# Feedback.net
KiCad netlist of a schematic drawn in Altium Designer
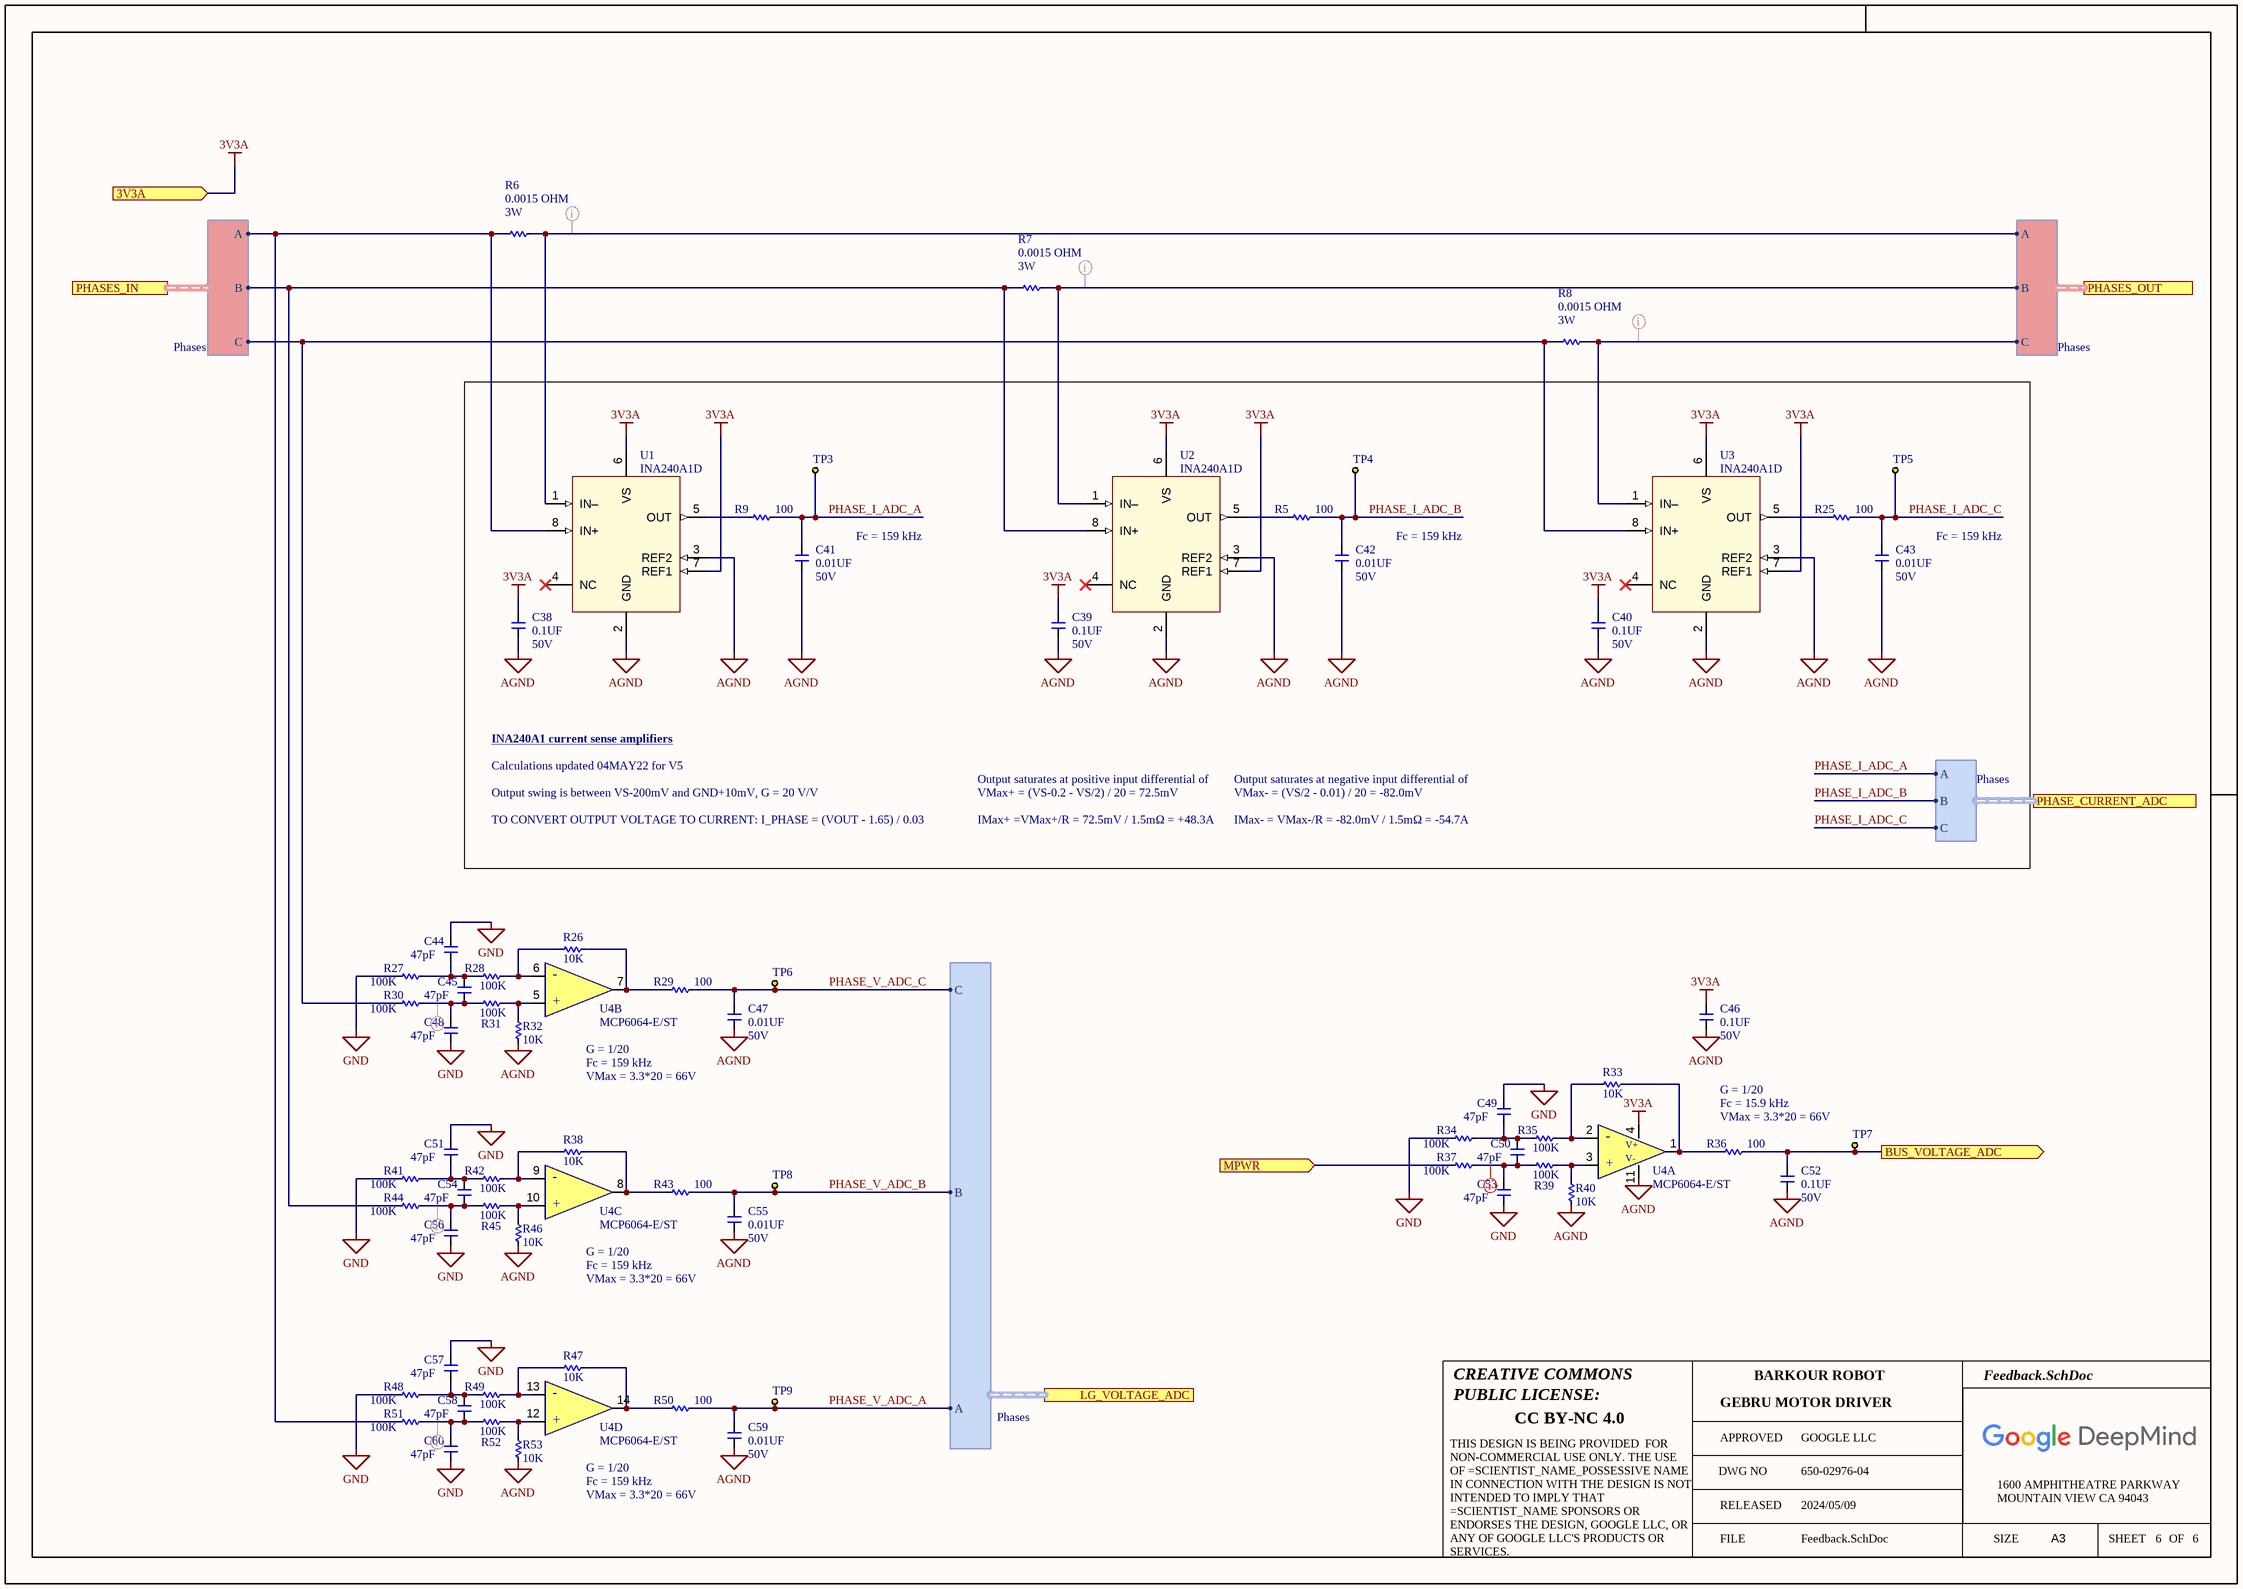
[diagram p0: Feedback.SchDoc]

(export (version "E")
  (design (tool "Eeschema 10.0.6"))
  (components
    (comp (ref "C38")
      (value "0.1UF")
      (footprint "C0402")
      (description "CAP, CER, X5R, 0.1uF, 10%, 50V, 0402, 0.55mm")
      (fields (field (name "MFG") "YAGEO") (field (name "VOLTAGE") "50V") (field (name "TOLERANCE") "10%"))
      (libsource (lib "AltiumReleaseLibDB") (part "__Template_Cap"))
    )
    (comp (ref "C39")
      (value "0.1UF")
      (footprint "C0402")
      (description "CAP, CER, X5R, 0.1uF, 10%, 50V, 0402, 0.55mm")
      (fields (field (name "MFG") "YAGEO") (field (name "VOLTAGE") "50V") (field (name "TOLERANCE") "10%"))
      (libsource (lib "AltiumReleaseLibDB") (part "__Template_Cap"))
    )
    (comp (ref "C40")
      (value "0.1UF")
      (footprint "C0402")
      (description "CAP, CER, X5R, 0.1uF, 10%, 50V, 0402, 0.55mm")
      (fields (field (name "MFG") "YAGEO") (field (name "VOLTAGE") "50V") (field (name "TOLERANCE") "10%"))
      (libsource (lib "AltiumReleaseLibDB") (part "__Template_Cap"))
    )
    (comp (ref "C41")
      (value "0.01UF")
      (footprint "C0402")
      (description "CAP, CER, X7R, 0.01uF, 50V, 20%, 0402, 0.56mm T")
      (fields (field (name "MFG") "KEMET") (field (name "VOLTAGE") "50V") (field (name "TOLERANCE") "20%"))
      (libsource (lib "AltiumReleaseLibDB") (part "__Template_Cap"))
    )
    (comp (ref "C42")
      (value "0.01UF")
      (footprint "C0402")
      (description "CAP, CER, X7R, 0.01uF, 50V, 20%, 0402, 0.56mm T")
      (fields (field (name "MFG") "KEMET") (field (name "VOLTAGE") "50V") (field (name "TOLERANCE") "20%"))
      (libsource (lib "AltiumReleaseLibDB") (part "__Template_Cap"))
    )
    (comp (ref "C43")
      (value "0.01UF")
      (footprint "C0402")
      (description "CAP, CER, X7R, 0.01uF, 50V, 20%, 0402, 0.56mm T")
      (fields (field (name "MFG") "KEMET") (field (name "VOLTAGE") "50V") (field (name "TOLERANCE") "20%"))
      (libsource (lib "AltiumReleaseLibDB") (part "__Template_Cap"))
    )
    (comp (ref "C44")
      (value "47pF")
      (footprint "C0402")
      (description "CAP, CER, C0G, 47PF, 5%, 50V, 0402")
      (fields (field (name "MFG") "TDK") (field (name "VOLTAGE") "50V"))
      (libsource (lib "AltiumReleaseLibDB") (part "__Template_Cap"))
    )
    (comp (ref "C45")
      (value "47pF")
      (footprint "C0402")
      (description "CAP, CER, C0G, 47PF, 5%, 50V, 0402")
      (fields (field (name "MFG") "TDK") (field (name "VOLTAGE") "50V"))
      (libsource (lib "AltiumReleaseLibDB") (part "__Template_Cap"))
    )
    (comp (ref "C46")
      (value "0.1UF")
      (footprint "C0402")
      (description "CAP, CER, X5R, 0.1uF, 10%, 50V, 0402, 0.55mm")
      (fields (field (name "MFG") "YAGEO") (field (name "VOLTAGE") "50V") (field (name "TOLERANCE") "10%"))
      (libsource (lib "AltiumReleaseLibDB") (part "__Template_Cap"))
    )
    (comp (ref "C47")
      (value "0.01UF")
      (footprint "C0402")
      (description "CAP, CER, X7R, 0.01uF, 50V, 20%, 0402, 0.56mm T")
      (fields (field (name "MFG") "KEMET") (field (name "VOLTAGE") "50V") (field (name "TOLERANCE") "20%"))
      (libsource (lib "AltiumReleaseLibDB") (part "__Template_Cap"))
    )
    (comp (ref "C48")
      (value "47pF")
      (footprint "C0402")
      (description "CAP, CER, C0G, 47PF, 5%, 50V, 0402")
      (fields (field (name "MFG") "TDK") (field (name "VOLTAGE") "50V"))
      (libsource (lib "AltiumReleaseLibDB") (part "__Template_Cap"))
    )
    (comp (ref "C49")
      (value "47pF")
      (footprint "C0402")
      (description "CAP, CER, C0G, 47PF, 5%, 50V, 0402")
      (fields (field (name "MFG") "TDK") (field (name "VOLTAGE") "50V"))
      (libsource (lib "AltiumReleaseLibDB") (part "__Template_Cap"))
    )
    (comp (ref "C50")
      (value "47pF")
      (footprint "C0402")
      (description "CAP, CER, C0G, 47PF, 5%, 50V, 0402")
      (fields (field (name "MFG") "TDK") (field (name "VOLTAGE") "50V"))
      (libsource (lib "AltiumReleaseLibDB") (part "__Template_Cap"))
    )
    (comp (ref "C51")
      (value "47pF")
      (footprint "C0402")
      (description "CAP, CER, C0G, 47PF, 5%, 50V, 0402")
      (fields (field (name "MFG") "TDK") (field (name "VOLTAGE") "50V"))
      (libsource (lib "AltiumReleaseLibDB") (part "__Template_Cap"))
    )
    (comp (ref "C52")
      (value "0.1UF")
      (footprint "C0402")
      (description "CAP, CER, X5R, 0.1uF, 10%, 50V, 0402, 0.55mm")
      (fields (field (name "MFG") "YAGEO") (field (name "VOLTAGE") "50V") (field (name "TOLERANCE") "10%"))
      (libsource (lib "AltiumReleaseLibDB") (part "__Template_Cap"))
    )
    (comp (ref "C53")
      (value "47pF")
      (footprint "C0402")
      (description "CAP, CER, C0G, 47PF, 5%, 50V, 0402")
      (fields (field (name "MFG") "TDK") (field (name "VOLTAGE") "50V"))
      (libsource (lib "AltiumReleaseLibDB") (part "__Template_Cap"))
    )
    (comp (ref "C54")
      (value "47pF")
      (footprint "C0402")
      (description "CAP, CER, C0G, 47PF, 5%, 50V, 0402")
      (fields (field (name "MFG") "TDK") (field (name "VOLTAGE") "50V"))
      (libsource (lib "AltiumReleaseLibDB") (part "__Template_Cap"))
    )
    (comp (ref "C55")
      (value "0.01UF")
      (footprint "C0402")
      (description "CAP, CER, X7R, 0.01uF, 50V, 20%, 0402, 0.56mm T")
      (fields (field (name "MFG") "KEMET") (field (name "VOLTAGE") "50V") (field (name "TOLERANCE") "20%"))
      (libsource (lib "AltiumReleaseLibDB") (part "__Template_Cap"))
    )
    (comp (ref "C56")
      (value "47pF")
      (footprint "C0402")
      (description "CAP, CER, C0G, 47PF, 5%, 50V, 0402")
      (fields (field (name "MFG") "TDK") (field (name "VOLTAGE") "50V"))
      (libsource (lib "AltiumReleaseLibDB") (part "__Template_Cap"))
    )
    (comp (ref "C57")
      (value "47pF")
      (footprint "C0402")
      (description "CAP, CER, C0G, 47PF, 5%, 50V, 0402")
      (fields (field (name "MFG") "TDK") (field (name "VOLTAGE") "50V"))
      (libsource (lib "AltiumReleaseLibDB") (part "__Template_Cap"))
    )
    (comp (ref "C58")
      (value "47pF")
      (footprint "C0402")
      (description "CAP, CER, C0G, 47PF, 5%, 50V, 0402")
      (fields (field (name "MFG") "TDK") (field (name "VOLTAGE") "50V"))
      (libsource (lib "AltiumReleaseLibDB") (part "__Template_Cap"))
    )
    (comp (ref "C59")
      (value "0.01UF")
      (footprint "C0402")
      (description "CAP, CER, X7R, 0.01uF, 50V, 20%, 0402, 0.56mm T")
      (fields (field (name "MFG") "KEMET") (field (name "VOLTAGE") "50V") (field (name "TOLERANCE") "20%"))
      (libsource (lib "AltiumReleaseLibDB") (part "__Template_Cap"))
    )
    (comp (ref "C60")
      (value "47pF")
      (footprint "C0402")
      (description "CAP, CER, C0G, 47PF, 5%, 50V, 0402")
      (fields (field (name "MFG") "TDK") (field (name "VOLTAGE") "50V"))
      (libsource (lib "AltiumReleaseLibDB") (part "__Template_Cap"))
    )
    (comp (ref "R5")
      (value "100")
      (footprint "RES 0402_1005 RF")
      (description "RES, 100, 1%, 1/10W, 0402, AUTO GRADE")
      (fields (field (name "MFG") "PANASONIC") (field (name "POWER") "1/10W"))
      (libsource (lib "AltiumReleaseLibDB") (part "__Template_Resistor"))
    )
    (comp (ref "R6")
      (value "0.0015 OHM")
      (footprint "R2512_H0.8MM")
      (description "RES, 0.0015, 1%, 3W, 2512")
      (fields
        (field (name "MFG") "TE Connectivity Passive Product")
        (field (name "POWER") "3W")
        (field (name "TOLERANCE") "1%")
      )
      (libsource (lib "AltiumReleaseLibDB") (part "__Template_Resistor"))
    )
    (comp (ref "R7")
      (value "0.0015 OHM")
      (footprint "R2512_H0.8MM")
      (description "RES, 0.0015, 1%, 3W, 2512")
      (fields
        (field (name "MFG") "TE Connectivity Passive Product")
        (field (name "POWER") "3W")
        (field (name "TOLERANCE") "1%")
      )
      (libsource (lib "AltiumReleaseLibDB") (part "__Template_Resistor"))
    )
    (comp (ref "R8")
      (value "0.0015 OHM")
      (footprint "R2512_H0.8MM")
      (description "RES, 0.0015, 1%, 3W, 2512")
      (fields
        (field (name "MFG") "TE Connectivity Passive Product")
        (field (name "POWER") "3W")
        (field (name "TOLERANCE") "1%")
      )
      (libsource (lib "AltiumReleaseLibDB") (part "__Template_Resistor"))
    )
    (comp (ref "R9")
      (value "100")
      (footprint "R0402")
      (description "RES, 100, 1%, 1/10W, 0402, AUTO GRADE")
      (fields (field (name "MFG") "PANASONIC") (field (name "POWER") "1/10W"))
      (libsource (lib "AltiumReleaseLibDB") (part "__Template_Resistor"))
    )
    (comp (ref "R25")
      (value "100")
      (footprint "R0402")
      (description "RES, 100, 1%, 1/10W, 0402, AUTO GRADE")
      (fields (field (name "MFG") "PANASONIC") (field (name "POWER") "1/10W"))
      (libsource (lib "AltiumReleaseLibDB") (part "__Template_Resistor"))
    )
    (comp (ref "R26")
      (value "10K")
      (footprint "R0402")
      (description "RES, 10K, 1%, 1/10W, 0402, AUTOGRADE")
      (fields (field (name "MFG") "PANASONIC") (field (name "POWER") "1/10W"))
      (libsource (lib "AltiumReleaseLibDB") (part "__Template_Resistor"))
    )
    (comp (ref "R27")
      (value "100K")
      (footprint "R0603")
      (description "RES, 100K, 1%, 1/10W, 0603, AUTO GRADE")
      (fields (field (name "MFG") "PANASONIC") (field (name "POWER") "1/10W"))
      (libsource (lib "AltiumReleaseLibDB") (part "__Template_Resistor"))
    )
    (comp (ref "R28")
      (value "100K")
      (footprint "R0603")
      (description "RES, 100K, 1%, 1/10W, 0603, AUTO GRADE")
      (fields (field (name "MFG") "PANASONIC") (field (name "POWER") "1/10W"))
      (libsource (lib "AltiumReleaseLibDB") (part "__Template_Resistor"))
    )
    (comp (ref "R29")
      (value "100")
      (footprint "R0402")
      (description "RES, 100, 1%, 1/10W, 0402, AUTO GRADE")
      (fields (field (name "MFG") "PANASONIC") (field (name "POWER") "1/10W"))
      (libsource (lib "AltiumReleaseLibDB") (part "__Template_Resistor"))
    )
    (comp (ref "R30")
      (value "100K")
      (footprint "R0603")
      (description "RES, 100K, 1%, 1/10W, 0603, AUTO GRADE")
      (fields (field (name "MFG") "PANASONIC") (field (name "POWER") "1/10W"))
      (libsource (lib "AltiumReleaseLibDB") (part "__Template_Resistor"))
    )
    (comp (ref "R31")
      (value "100K")
      (footprint "R0603")
      (description "RES, 100K, 1%, 1/10W, 0603, AUTO GRADE")
      (fields (field (name "MFG") "PANASONIC") (field (name "POWER") "1/10W"))
      (libsource (lib "AltiumReleaseLibDB") (part "__Template_Resistor"))
    )
    (comp (ref "R32")
      (value "10K")
      (footprint "R0402")
      (description "RES, 10K, 1%, 1/10W, 0402, AUTOGRADE")
      (fields (field (name "MFG") "PANASONIC") (field (name "POWER") "1/10W"))
      (libsource (lib "AltiumReleaseLibDB") (part "__Template_Resistor"))
    )
    (comp (ref "R33")
      (value "10K")
      (footprint "R0402")
      (description "RES, 10K, 1%, 1/10W, 0402, AUTOGRADE")
      (fields (field (name "MFG") "PANASONIC") (field (name "POWER") "1/10W"))
      (libsource (lib "AltiumReleaseLibDB") (part "__Template_Resistor"))
    )
    (comp (ref "R34")
      (value "100K")
      (footprint "R0603")
      (description "RES, 100K, 1%, 1/10W, 0603, AUTO GRADE")
      (fields (field (name "MFG") "PANASONIC") (field (name "POWER") "1/10W"))
      (libsource (lib "AltiumReleaseLibDB") (part "__Template_Resistor"))
    )
    (comp (ref "R35")
      (value "100K")
      (footprint "R0603")
      (description "RES, 100K, 1%, 1/10W, 0603, AUTO GRADE")
      (fields (field (name "MFG") "PANASONIC") (field (name "POWER") "1/10W"))
      (libsource (lib "AltiumReleaseLibDB") (part "__Template_Resistor"))
    )
    (comp (ref "R36")
      (value "100")
      (footprint "R0402")
      (description "RES, 100, 1%, 1/10W, 0402, AUTO GRADE")
      (fields (field (name "MFG") "PANASONIC") (field (name "POWER") "1/10W"))
      (libsource (lib "AltiumReleaseLibDB") (part "__Template_Resistor"))
    )
    (comp (ref "R37")
      (value "100K")
      (footprint "R0603")
      (description "RES, 100K, 1%, 1/10W, 0603, AUTO GRADE")
      (fields (field (name "MFG") "PANASONIC") (field (name "POWER") "1/10W"))
      (libsource (lib "AltiumReleaseLibDB") (part "__Template_Resistor"))
    )
    (comp (ref "R38")
      (value "10K")
      (footprint "R0402")
      (description "RES, 10K, 1%, 1/10W, 0402, AUTOGRADE")
      (fields (field (name "MFG") "PANASONIC") (field (name "POWER") "1/10W"))
      (libsource (lib "AltiumReleaseLibDB") (part "__Template_Resistor"))
    )
    (comp (ref "R39")
      (value "100K")
      (footprint "R0603")
      (description "RES, 100K, 1%, 1/10W, 0603, AUTO GRADE")
      (fields (field (name "MFG") "PANASONIC") (field (name "POWER") "1/10W"))
      (libsource (lib "AltiumReleaseLibDB") (part "__Template_Resistor"))
    )
    (comp (ref "R40")
      (value "10K")
      (footprint "R0402")
      (description "RES, 10K, 1%, 1/10W, 0402, AUTOGRADE")
      (fields (field (name "MFG") "PANASONIC") (field (name "POWER") "1/10W"))
      (libsource (lib "AltiumReleaseLibDB") (part "__Template_Resistor"))
    )
    (comp (ref "R41")
      (value "100K")
      (footprint "R0603")
      (description "RES, 100K, 1%, 1/10W, 0603, AUTO GRADE")
      (fields (field (name "MFG") "PANASONIC") (field (name "POWER") "1/10W"))
      (libsource (lib "AltiumReleaseLibDB") (part "__Template_Resistor"))
    )
    (comp (ref "R42")
      (value "100K")
      (footprint "R0603")
      (description "RES, 100K, 1%, 1/10W, 0603, AUTO GRADE")
      (fields (field (name "MFG") "PANASONIC") (field (name "POWER") "1/10W"))
      (libsource (lib "AltiumReleaseLibDB") (part "__Template_Resistor"))
    )
    (comp (ref "R43")
      (value "100")
      (footprint "R0402")
      (description "RES, 100, 1%, 1/10W, 0402, AUTO GRADE")
      (fields (field (name "MFG") "PANASONIC") (field (name "POWER") "1/10W"))
      (libsource (lib "AltiumReleaseLibDB") (part "__Template_Resistor"))
    )
    (comp (ref "R44")
      (value "100K")
      (footprint "R0603")
      (description "RES, 100K, 1%, 1/10W, 0603, AUTO GRADE")
      (fields (field (name "MFG") "PANASONIC") (field (name "POWER") "1/10W"))
      (libsource (lib "AltiumReleaseLibDB") (part "__Template_Resistor"))
    )
    (comp (ref "R45")
      (value "100K")
      (footprint "R0603")
      (description "RES, 100K, 1%, 1/10W, 0603, AUTO GRADE")
      (fields (field (name "MFG") "PANASONIC") (field (name "POWER") "1/10W"))
      (libsource (lib "AltiumReleaseLibDB") (part "__Template_Resistor"))
    )
    (comp (ref "R46")
      (value "10K")
      (footprint "R0402")
      (description "RES, 10K, 1%, 1/10W, 0402, AUTOGRADE")
      (fields (field (name "MFG") "PANASONIC") (field (name "POWER") "1/10W"))
      (libsource (lib "AltiumReleaseLibDB") (part "__Template_Resistor"))
    )
    (comp (ref "R47")
      (value "10K")
      (footprint "R0402")
      (description "RES, 10K, 1%, 1/10W, 0402, AUTOGRADE")
      (fields (field (name "MFG") "PANASONIC") (field (name "POWER") "1/10W"))
      (libsource (lib "AltiumReleaseLibDB") (part "__Template_Resistor"))
    )
    (comp (ref "R48")
      (value "100K")
      (footprint "R0603")
      (description "RES, 100K, 1%, 1/10W, 0603, AUTO GRADE")
      (fields (field (name "MFG") "PANASONIC") (field (name "POWER") "1/10W"))
      (libsource (lib "AltiumReleaseLibDB") (part "__Template_Resistor"))
    )
    (comp (ref "R49")
      (value "100K")
      (footprint "R0603")
      (description "RES, 100K, 1%, 1/10W, 0603, AUTO GRADE")
      (fields (field (name "MFG") "PANASONIC") (field (name "POWER") "1/10W"))
      (libsource (lib "AltiumReleaseLibDB") (part "__Template_Resistor"))
    )
    (comp (ref "R50")
      (value "100")
      (footprint "R0402")
      (description "RES, 100, 1%, 1/10W, 0402, AUTO GRADE")
      (fields (field (name "MFG") "PANASONIC") (field (name "POWER") "1/10W"))
      (libsource (lib "AltiumReleaseLibDB") (part "__Template_Resistor"))
    )
    (comp (ref "R51")
      (value "100K")
      (footprint "R0603")
      (description "RES, 100K, 1%, 1/10W, 0603, AUTO GRADE")
      (fields (field (name "MFG") "PANASONIC") (field (name "POWER") "1/10W"))
      (libsource (lib "AltiumReleaseLibDB") (part "__Template_Resistor"))
    )
    (comp (ref "R52")
      (value "100K")
      (footprint "R0603")
      (description "RES, 100K, 1%, 1/10W, 0603, AUTO GRADE")
      (fields (field (name "MFG") "PANASONIC") (field (name "POWER") "1/10W"))
      (libsource (lib "AltiumReleaseLibDB") (part "__Template_Resistor"))
    )
    (comp (ref "R53")
      (value "10K")
      (footprint "R0402")
      (description "RES, 10K, 1%, 1/10W, 0402, AUTOGRADE")
      (fields (field (name "MFG") "PANASONIC") (field (name "POWER") "1/10W"))
      (libsource (lib "AltiumReleaseLibDB") (part "__Template_Resistor"))
    )
    (comp (ref "TP3")
      (value "TEST_KEYSTONE5015")
      (footprint "TP_KEYSTONE_5015")
      (description "PC TEST POINT MINIATURE SMT")
      (fields
        (field (name "MANUFACTURER") "Keystone Electronics")
        (field (name "MANUFACTURER PART NUMBER") "5015")
      )
      (libsource (lib "miscellaneous") (part "TEST_KEYSTONE5015"))
    )
    (comp (ref "TP4")
      (value "TEST_KEYSTONE5015")
      (footprint "TP_KEYSTONE_5015")
      (description "PC TEST POINT MINIATURE SMT")
      (fields
        (field (name "MANUFACTURER") "Keystone Electronics")
        (field (name "MANUFACTURER PART NUMBER") "5015")
      )
      (libsource (lib "miscellaneous") (part "TEST_KEYSTONE5015"))
    )
    (comp (ref "TP5")
      (value "TEST_KEYSTONE5015")
      (footprint "TP_KEYSTONE_5015")
      (description "PC TEST POINT MINIATURE SMT")
      (fields
        (field (name "MANUFACTURER") "Keystone Electronics")
        (field (name "MANUFACTURER PART NUMBER") "5015")
      )
      (libsource (lib "miscellaneous") (part "TEST_KEYSTONE5015"))
    )
    (comp (ref "TP6")
      (value "TEST_KEYSTONE5015")
      (footprint "TP_KEYSTONE_5015")
      (description "PC TEST POINT MINIATURE SMT")
      (fields
        (field (name "MANUFACTURER") "Keystone Electronics")
        (field (name "MANUFACTURER PART NUMBER") "5015")
      )
      (libsource (lib "miscellaneous") (part "TEST_KEYSTONE5015"))
    )
    (comp (ref "TP7")
      (value "TEST_KEYSTONE5015")
      (footprint "TP_KEYSTONE_5015")
      (description "PC TEST POINT MINIATURE SMT")
      (fields
        (field (name "MANUFACTURER") "Keystone Electronics")
        (field (name "MANUFACTURER PART NUMBER") "5015")
      )
      (libsource (lib "miscellaneous") (part "TEST_KEYSTONE5015"))
    )
    (comp (ref "TP8")
      (value "TEST_KEYSTONE5015")
      (footprint "TP_KEYSTONE_5015")
      (description "PC TEST POINT MINIATURE SMT")
      (fields
        (field (name "MANUFACTURER") "Keystone Electronics")
        (field (name "MANUFACTURER PART NUMBER") "5015")
      )
      (libsource (lib "miscellaneous") (part "TEST_KEYSTONE5015"))
    )
    (comp (ref "TP9")
      (value "TEST_KEYSTONE5015")
      (footprint "TP_KEYSTONE_5015")
      (description "PC TEST POINT MINIATURE SMT")
      (fields
        (field (name "MANUFACTURER") "Keystone Electronics")
        (field (name "MANUFACTURER PART NUMBER") "5015")
      )
      (libsource (lib "miscellaneous") (part "TEST_KEYSTONE5015"))
    )
    (comp (ref "U1")
      (value "INA240A1D")
      (footprint "TI SOIC-8 D0008A")
      (fields (field (name "MANUFACTURER") "Texas Instruments"))
      (libsource (lib "MiscSch1") (part "INA240A1"))
    )
    (comp (ref "U2")
      (value "INA240A1D")
      (footprint "TI SOIC-8 D0008A")
      (fields (field (name "MANUFACTURER") "Texas Instruments"))
      (libsource (lib "MiscSch1") (part "INA240A1"))
    )
    (comp (ref "U3")
      (value "INA240A1D")
      (footprint "TI SOIC-8 D0008A")
      (fields (field (name "MANUFACTURER") "Texas Instruments"))
      (libsource (lib "MiscSch1") (part "INA240A1"))
    )
    (comp (ref "U4")
      (value "MCP6064")
      (footprint "14TSSOP65")
      (description "Microchip MCP6064-E/ST; Quad Op Amp; 0.73MHz CMOS; Rail to Rail; 3V; 5V; 14-Pin TSSOP")
      (fields
        (field (name "MANUFACTURER") "Microchip")
        (field (name "MANUFACTURER PART NUMBER") "MCP6064-E/ST")
      )
      (libsource (lib "MiscSch1") (part "MICROCHIP_MCP6064"))
    )
  )
  (nets
    (net (code "2") (name "/BUS_VOLTAGE_ADC") (class "Default")
      (node (ref "C52") (pin "1") (pintype "passive"))
      (node (ref "R36") (pin "2") (pintype "passive"))
      (node (ref "TP7") (pin "1") (pintype "passive"))
    )
    (net (code "3") (name "/MPWR") (class "Default") (node (ref "R37") (pin "1") (pintype "passive")))
    (net (code "4") (name "/PHASE_I_ADC_A") (class "Default")
      (node (ref "C41") (pin "1") (pintype "passive"))
      (node (ref "R9") (pin "2") (pintype "passive"))
      (node (ref "TP3") (pin "1") (pintype "passive"))
    )
    (net (code "5") (name "/PHASE_I_ADC_B") (class "Default")
      (node (ref "C42") (pin "1") (pintype "passive"))
      (node (ref "R5") (pin "2") (pintype "passive"))
      (node (ref "TP4") (pin "1") (pintype "passive"))
    )
    (net (code "6") (name "/PHASE_I_ADC_C") (class "Default")
      (node (ref "C43") (pin "1") (pintype "passive"))
      (node (ref "R25") (pin "2") (pintype "passive"))
      (node (ref "TP5") (pin "1") (pintype "passive"))
    )
    (net (code "7") (name "/PHASE_V_ADC_A") (class "Default")
      (node (ref "C59") (pin "1") (pintype "passive"))
      (node (ref "R50") (pin "2") (pintype "passive"))
      (node (ref "TP9") (pin "1") (pintype "passive"))
    )
    (net (code "8") (name "/PHASE_V_ADC_B") (class "Default")
      (node (ref "C55") (pin "1") (pintype "passive"))
      (node (ref "R43") (pin "2") (pintype "passive"))
      (node (ref "TP8") (pin "1") (pintype "passive"))
    )
    (net (code "9") (name "/PHASE_V_ADC_C") (class "Default")
      (node (ref "C47") (pin "1") (pintype "passive"))
      (node (ref "R29") (pin "2") (pintype "passive"))
      (node (ref "TP6") (pin "1") (pintype "passive"))
    )
    (net (code "11") (name "3V3A") (class "Default")
      (node (ref "C38") (pin "1") (pintype "passive"))
      (node (ref "C39") (pin "1") (pintype "passive"))
      (node (ref "C40") (pin "1") (pintype "passive"))
      (node (ref "C46") (pin "1") (pintype "passive"))
      (node (ref "U1") (pin "6") (pinfunction "VS_6") (pintype "power_in"))
      (node (ref "U1") (pin "7") (pinfunction "REF1_7") (pintype "input"))
      (node (ref "U2") (pin "6") (pinfunction "VS_6") (pintype "power_in"))
      (node (ref "U2") (pin "7") (pinfunction "REF1_7") (pintype "input"))
      (node (ref "U3") (pin "6") (pinfunction "VS_6") (pintype "power_in"))
      (node (ref "U3") (pin "7") (pinfunction "REF1_7") (pintype "input"))
      (node (ref "U4") (pin "4") (pinfunction "4_4") (pintype "passive"))
    )
    (net (code "12") (name "AGND") (class "Default")
      (node (ref "C38") (pin "2") (pintype "passive"))
      (node (ref "C39") (pin "2") (pintype "passive"))
      (node (ref "C40") (pin "2") (pintype "passive"))
      (node (ref "C41") (pin "2") (pintype "passive"))
      (node (ref "C42") (pin "2") (pintype "passive"))
      (node (ref "C43") (pin "2") (pintype "passive"))
      (node (ref "C46") (pin "2") (pintype "passive"))
      (node (ref "C47") (pin "2") (pintype "passive"))
      (node (ref "C52") (pin "2") (pintype "passive"))
      (node (ref "C55") (pin "2") (pintype "passive"))
      (node (ref "C59") (pin "2") (pintype "passive"))
      (node (ref "R32") (pin "1") (pintype "passive"))
      (node (ref "R40") (pin "1") (pintype "passive"))
      (node (ref "R46") (pin "1") (pintype "passive"))
      (node (ref "R53") (pin "1") (pintype "passive"))
      (node (ref "U1") (pin "2") (pinfunction "GND_2") (pintype "power_in"))
      (node (ref "U1") (pin "3") (pinfunction "REF2_3") (pintype "input"))
      (node (ref "U2") (pin "2") (pinfunction "GND_2") (pintype "power_in"))
      (node (ref "U2") (pin "3") (pinfunction "REF2_3") (pintype "input"))
      (node (ref "U3") (pin "2") (pinfunction "GND_2") (pintype "power_in"))
      (node (ref "U3") (pin "3") (pinfunction "REF2_3") (pintype "input"))
      (node (ref "U4") (pin "11") (pinfunction "11_11") (pintype "passive"))
    )
    (net (code "13") (name "GND") (class "Default")
      (node (ref "C44") (pin "2") (pintype "passive"))
      (node (ref "C48") (pin "1") (pintype "passive"))
      (node (ref "C49") (pin "2") (pintype "passive"))
      (node (ref "C51") (pin "2") (pintype "passive"))
      (node (ref "C53") (pin "1") (pintype "passive"))
      (node (ref "C56") (pin "1") (pintype "passive"))
      (node (ref "C57") (pin "2") (pintype "passive"))
      (node (ref "C60") (pin "1") (pintype "passive"))
      (node (ref "R27") (pin "1") (pintype "passive"))
      (node (ref "R34") (pin "1") (pintype "passive"))
      (node (ref "R41") (pin "1") (pintype "passive"))
      (node (ref "R48") (pin "1") (pintype "passive"))
    )
    (net (code "14") (name "Net-(C44-Pad1)") (class "Default")
      (node (ref "C44") (pin "1") (pintype "passive"))
      (node (ref "C45") (pin "2") (pintype "passive"))
      (node (ref "R27") (pin "2") (pintype "passive"))
      (node (ref "R28") (pin "1") (pintype "passive"))
    )
    (net (code "15") (name "Net-(C45-Pad1)") (class "Default")
      (node (ref "C45") (pin "1") (pintype "passive"))
      (node (ref "C48") (pin "2") (pintype "passive"))
      (node (ref "R30") (pin "2") (pintype "passive"))
      (node (ref "R31") (pin "1") (pintype "passive"))
    )
    (net (code "16") (name "Net-(C49-Pad1)") (class "Default")
      (node (ref "C49") (pin "1") (pintype "passive"))
      (node (ref "C50") (pin "2") (pintype "passive"))
      (node (ref "R34") (pin "2") (pintype "passive"))
      (node (ref "R35") (pin "1") (pintype "passive"))
    )
    (net (code "17") (name "Net-(C50-Pad1)") (class "Default")
      (node (ref "C50") (pin "1") (pintype "passive"))
      (node (ref "C53") (pin "2") (pintype "passive"))
      (node (ref "R37") (pin "2") (pintype "passive"))
      (node (ref "R39") (pin "1") (pintype "passive"))
    )
    (net (code "18") (name "Net-(C51-Pad1)") (class "Default")
      (node (ref "C51") (pin "1") (pintype "passive"))
      (node (ref "C54") (pin "2") (pintype "passive"))
      (node (ref "R41") (pin "2") (pintype "passive"))
      (node (ref "R42") (pin "1") (pintype "passive"))
    )
    (net (code "19") (name "Net-(C54-Pad1)") (class "Default")
      (node (ref "C54") (pin "1") (pintype "passive"))
      (node (ref "C56") (pin "2") (pintype "passive"))
      (node (ref "R44") (pin "2") (pintype "passive"))
      (node (ref "R45") (pin "1") (pintype "passive"))
    )
    (net (code "20") (name "Net-(C57-Pad1)") (class "Default")
      (node (ref "C57") (pin "1") (pintype "passive"))
      (node (ref "C58") (pin "2") (pintype "passive"))
      (node (ref "R48") (pin "2") (pintype "passive"))
      (node (ref "R49") (pin "1") (pintype "passive"))
    )
    (net (code "21") (name "Net-(C58-Pad1)") (class "Default")
      (node (ref "C58") (pin "1") (pintype "passive"))
      (node (ref "C60") (pin "2") (pintype "passive"))
      (node (ref "R51") (pin "2") (pintype "passive"))
      (node (ref "R52") (pin "1") (pintype "passive"))
    )
    (net (code "22") (name "Net-(R26-Pad1)") (class "Default")
      (node (ref "R26") (pin "1") (pintype "passive"))
      (node (ref "R29") (pin "1") (pintype "passive"))
      (node (ref "U4") (pin "7") (pinfunction "7_7") (pintype "passive"))
    )
    (net (code "23") (name "Net-(R26-Pad2)") (class "Default")
      (node (ref "R26") (pin "2") (pintype "passive"))
      (node (ref "R28") (pin "2") (pintype "passive"))
      (node (ref "U4") (pin "6") (pinfunction "6_6") (pintype "passive"))
    )
    (net (code "24") (name "Net-(R31-Pad2)") (class "Default")
      (node (ref "R31") (pin "2") (pintype "passive"))
      (node (ref "R32") (pin "2") (pintype "passive"))
      (node (ref "U4") (pin "5") (pinfunction "5_5") (pintype "passive"))
    )
    (net (code "25") (name "Net-(R33-Pad1)") (class "Default")
      (node (ref "R33") (pin "1") (pintype "passive"))
      (node (ref "R36") (pin "1") (pintype "passive"))
      (node (ref "U4") (pin "1") (pinfunction "1_1") (pintype "passive"))
    )
    (net (code "26") (name "Net-(R33-Pad2)") (class "Default")
      (node (ref "R33") (pin "2") (pintype "passive"))
      (node (ref "R35") (pin "2") (pintype "passive"))
      (node (ref "U4") (pin "2") (pinfunction "2_2") (pintype "passive"))
    )
    (net (code "27") (name "Net-(R38-Pad1)") (class "Default")
      (node (ref "R38") (pin "1") (pintype "passive"))
      (node (ref "R43") (pin "1") (pintype "passive"))
      (node (ref "U4") (pin "8") (pinfunction "8_8") (pintype "passive"))
    )
    (net (code "28") (name "Net-(R38-Pad2)") (class "Default")
      (node (ref "R38") (pin "2") (pintype "passive"))
      (node (ref "R42") (pin "2") (pintype "passive"))
      (node (ref "U4") (pin "9") (pinfunction "9_9") (pintype "passive"))
    )
    (net (code "29") (name "Net-(R39-Pad2)") (class "Default")
      (node (ref "R39") (pin "2") (pintype "passive"))
      (node (ref "R40") (pin "2") (pintype "passive"))
      (node (ref "U4") (pin "3") (pinfunction "3_3") (pintype "passive"))
    )
    (net (code "30") (name "Net-(R45-Pad2)") (class "Default")
      (node (ref "R45") (pin "2") (pintype "passive"))
      (node (ref "R46") (pin "2") (pintype "passive"))
      (node (ref "U4") (pin "10") (pinfunction "10_10") (pintype "passive"))
    )
    (net (code "31") (name "Net-(R47-Pad1)") (class "Default")
      (node (ref "R47") (pin "1") (pintype "passive"))
      (node (ref "R50") (pin "1") (pintype "passive"))
      (node (ref "U4") (pin "14") (pinfunction "14_14") (pintype "passive"))
    )
    (net (code "32") (name "Net-(R47-Pad2)") (class "Default")
      (node (ref "R47") (pin "2") (pintype "passive"))
      (node (ref "R49") (pin "2") (pintype "passive"))
      (node (ref "U4") (pin "13") (pinfunction "13_13") (pintype "passive"))
    )
    (net (code "33") (name "Net-(R52-Pad2)") (class "Default")
      (node (ref "R52") (pin "2") (pintype "passive"))
      (node (ref "R53") (pin "2") (pintype "passive"))
      (node (ref "U4") (pin "12") (pinfunction "12_12") (pintype "passive"))
    )
    (net (code "34") (name "Net-(U1-IN+)") (class "Default")
      (node (ref "R51") (pin "1") (pintype "passive"))
      (node (ref "R6") (pin "1") (pintype "passive"))
      (node (ref "U1") (pin "8") (pinfunction "IN+_8") (pintype "input"))
    )
    (net (code "35") (name "Net-(U1-IN–)") (class "Default")
      (node (ref "R6") (pin "2") (pintype "passive"))
      (node (ref "U1") (pin "1") (pinfunction "IN–_1") (pintype "input"))
    )
    (net (code "36") (name "Net-(U1-OUT)") (class "Default")
      (node (ref "R9") (pin "1") (pintype "passive"))
      (node (ref "U1") (pin "5") (pinfunction "OUT_5") (pintype "output"))
    )
    (net (code "37") (name "Net-(U2-IN+)") (class "Default")
      (node (ref "R44") (pin "1") (pintype "passive"))
      (node (ref "R7") (pin "1") (pintype "passive"))
      (node (ref "U2") (pin "8") (pinfunction "IN+_8") (pintype "input"))
    )
    (net (code "38") (name "Net-(U2-IN–)") (class "Default")
      (node (ref "R7") (pin "2") (pintype "passive"))
      (node (ref "U2") (pin "1") (pinfunction "IN–_1") (pintype "input"))
    )
    (net (code "39") (name "Net-(U2-OUT)") (class "Default")
      (node (ref "R5") (pin "1") (pintype "passive"))
      (node (ref "U2") (pin "5") (pinfunction "OUT_5") (pintype "output"))
    )
    (net (code "40") (name "Net-(U3-IN+)") (class "Default")
      (node (ref "R30") (pin "1") (pintype "passive"))
      (node (ref "R8") (pin "1") (pintype "passive"))
      (node (ref "U3") (pin "8") (pinfunction "IN+_8") (pintype "input"))
    )
    (net (code "41") (name "Net-(U3-IN–)") (class "Default")
      (node (ref "R8") (pin "2") (pintype "passive"))
      (node (ref "U3") (pin "1") (pinfunction "IN–_1") (pintype "input"))
    )
    (net (code "42") (name "Net-(U3-OUT)") (class "Default")
      (node (ref "R25") (pin "1") (pintype "passive"))
      (node (ref "U3") (pin "5") (pinfunction "OUT_5") (pintype "output"))
    )
    (net (code "43") (name "unconnected-(U1-NC-Pad4)") (class "Default")
      (node (ref "U1") (pin "4") (pinfunction "NC_4") (pintype "passive+no_connect"))
    )
    (net (code "44") (name "unconnected-(U2-NC-Pad4)") (class "Default")
      (node (ref "U2") (pin "4") (pinfunction "NC_4") (pintype "passive+no_connect"))
    )
    (net (code "45") (name "unconnected-(U3-NC-Pad4)") (class "Default")
      (node (ref "U3") (pin "4") (pinfunction "NC_4") (pintype "passive+no_connect"))
    )
  )
)
